# IRIS1304_v2_23.net
KiCad netlist of a schematic drawn in EAGLE
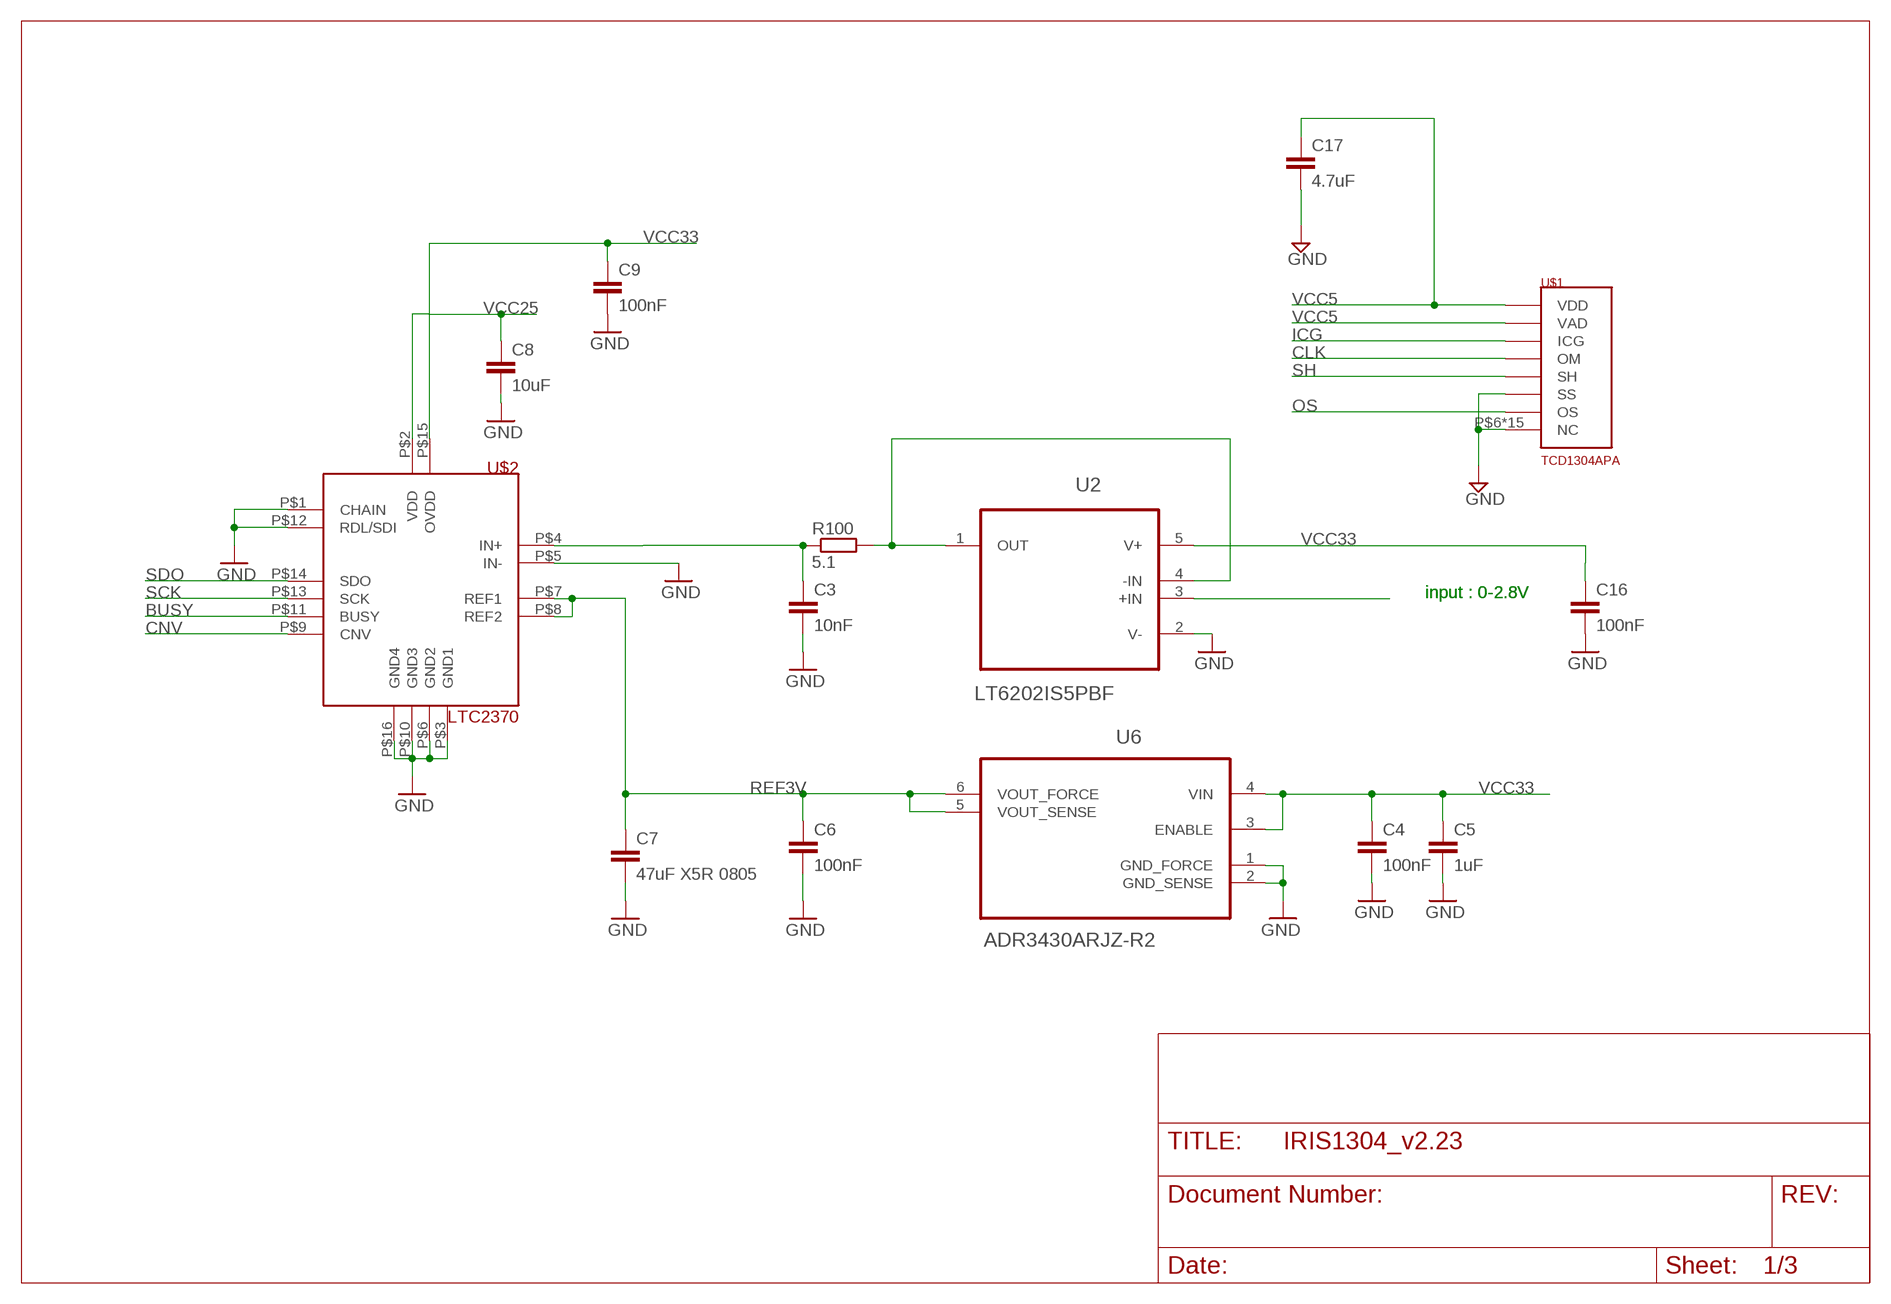
[diagram p0: schematic, sheet 1]
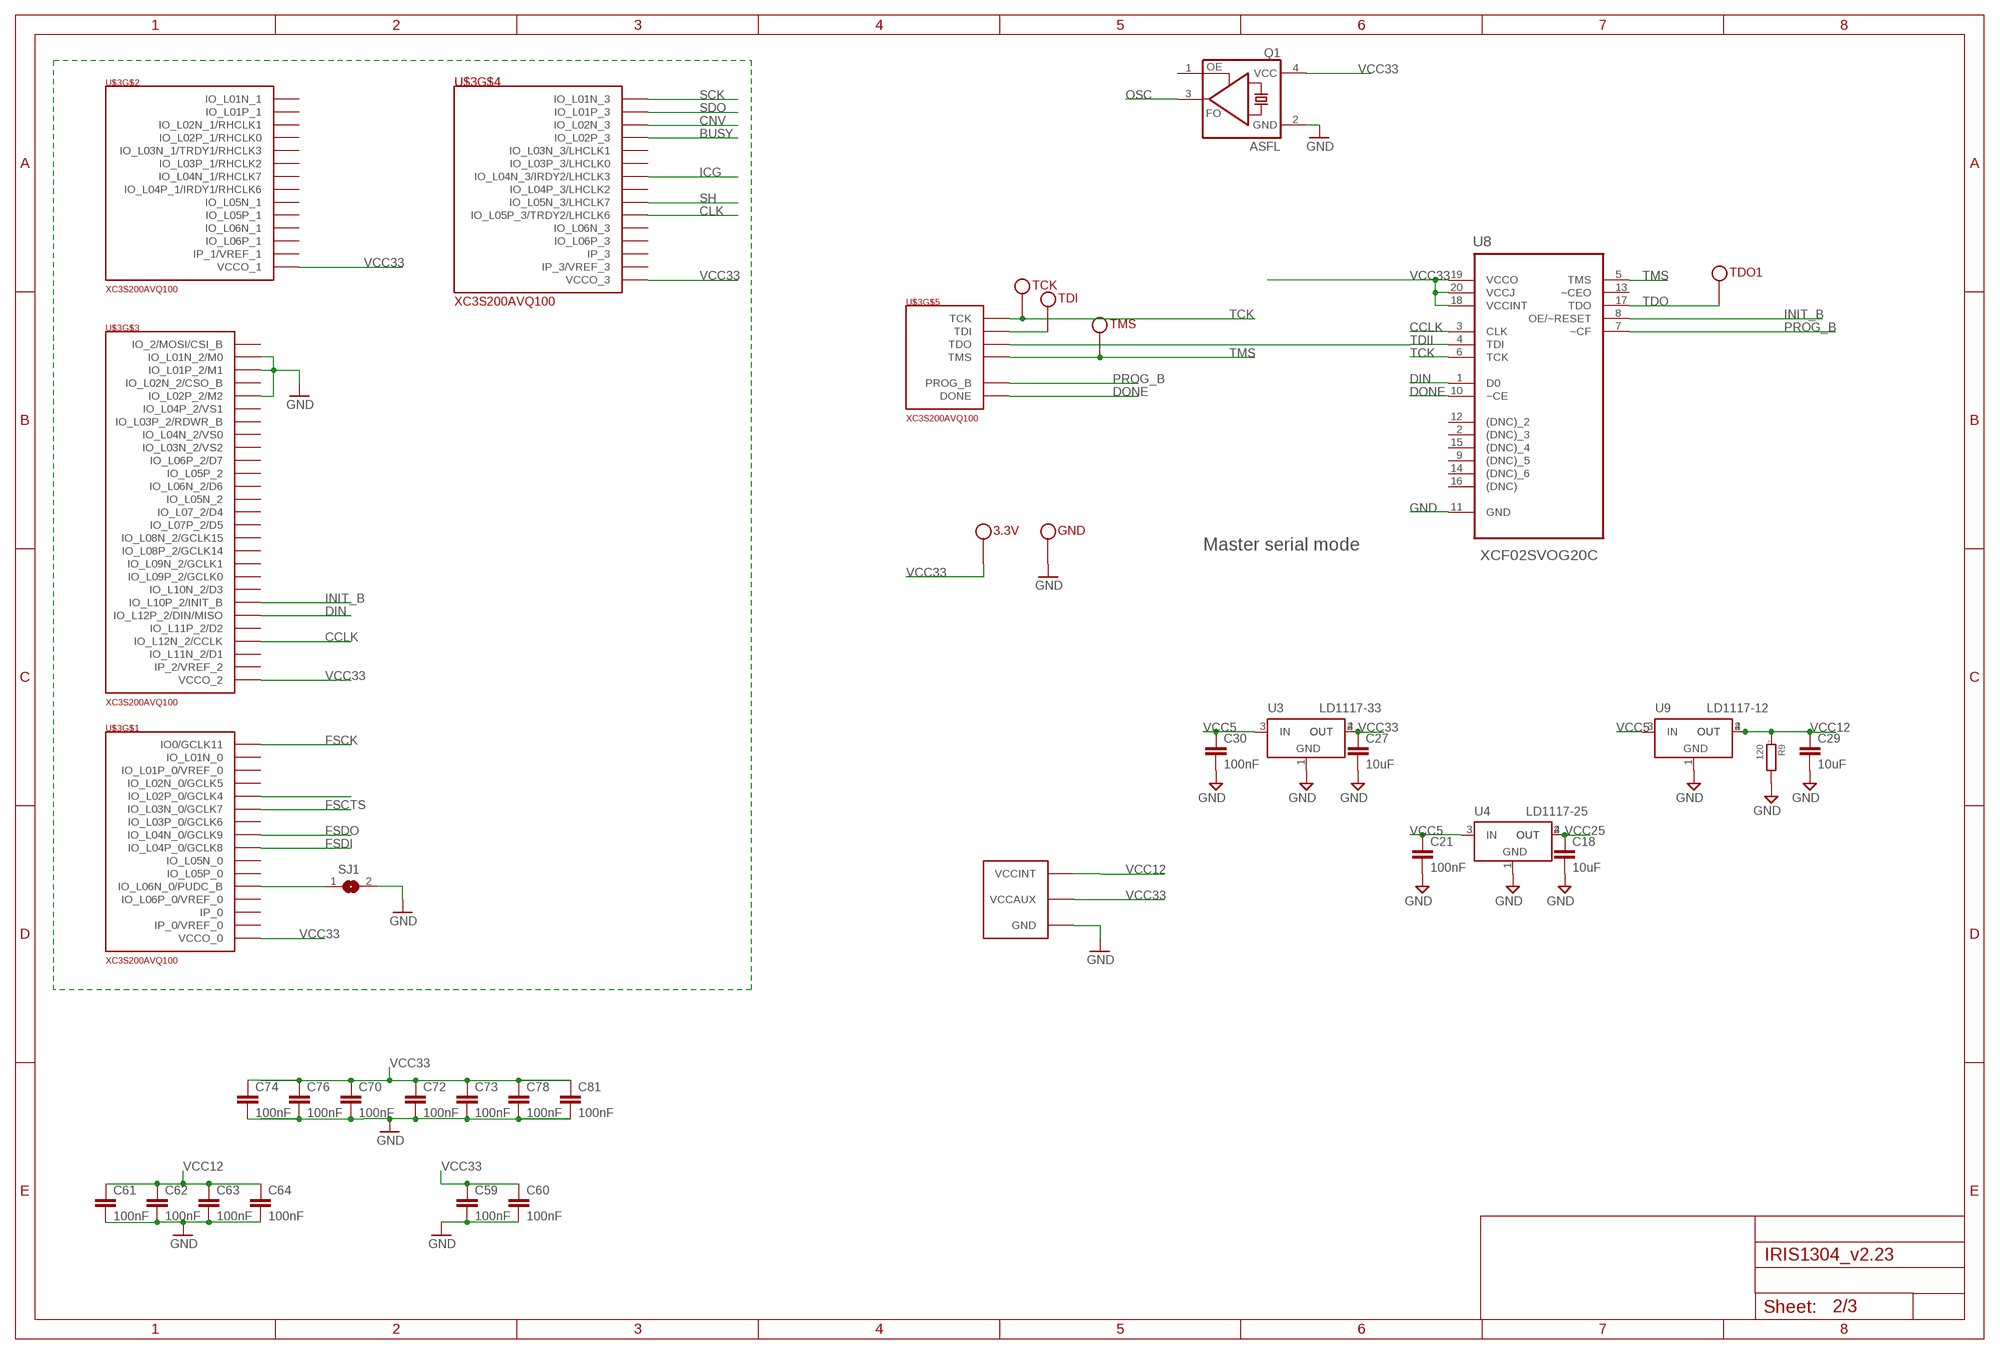
[diagram p1: schematic, sheet 2]
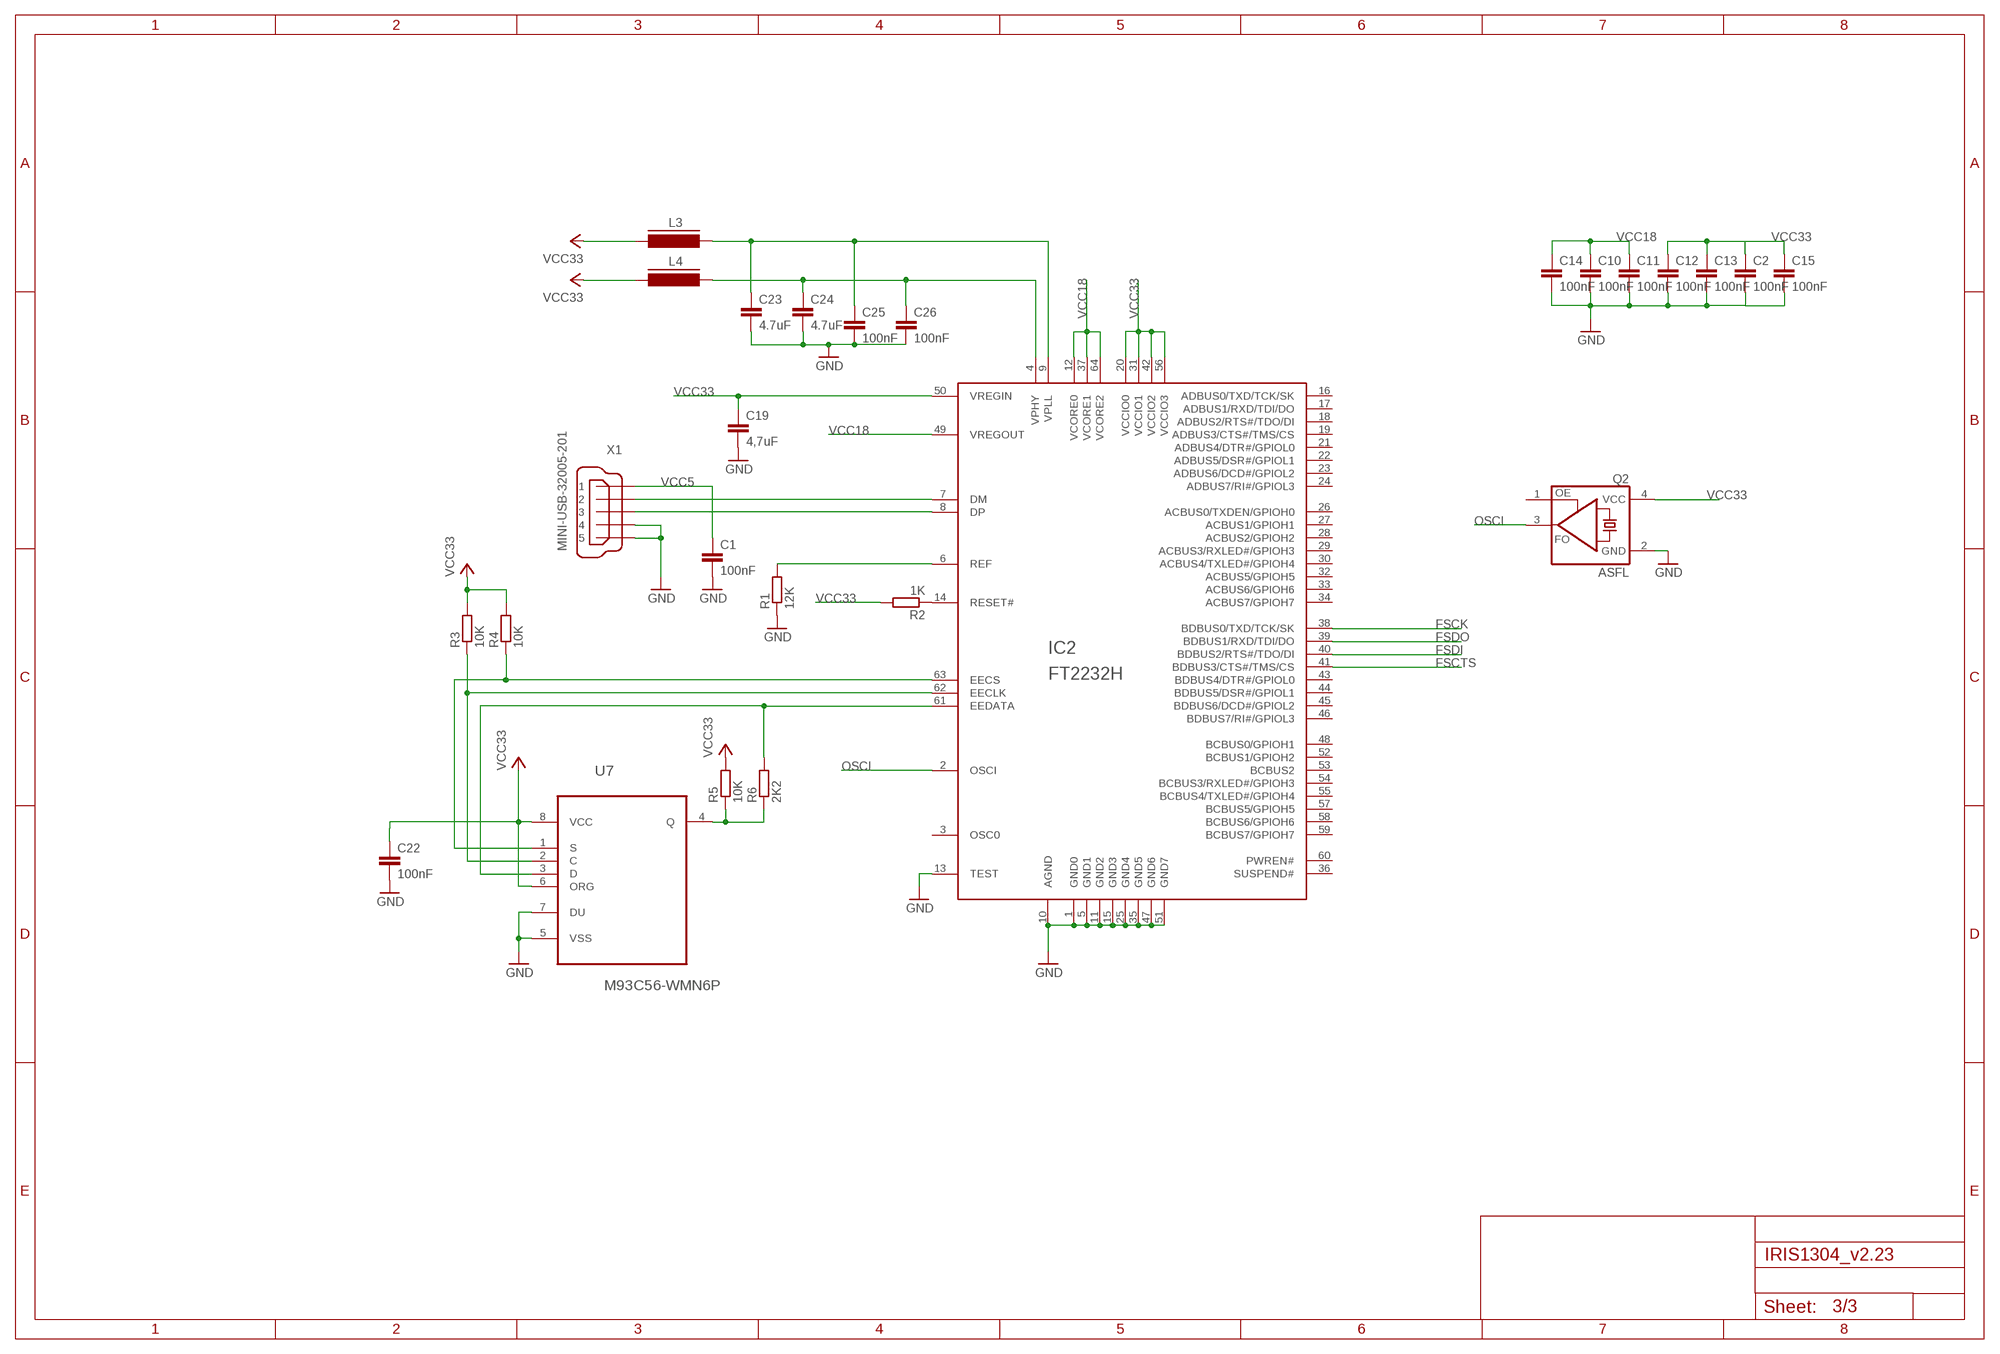
[diagram p2: schematic, sheet 3]

(export (version "E")
  (design (tool "Eeschema 10.0.6"))
  (components
    (comp (ref "C1")
      (value "100nF")
      (footprint "eagle-import:C0603")
      (fields (field (name "MF") "AVX") (field (name "MPN") "06033G104ZAT2A"))
      (libsource (lib "eagle-import") (part "C-EUC0603"))
    )
    (comp (ref "C2")
      (value "100nF")
      (footprint "eagle-import:C0603")
      (fields (field (name "MF") "AVX") (field (name "MPN") "06033G104ZAT2A"))
      (libsource (lib "eagle-import") (part "C-EUC0603"))
    )
    (comp (ref "C10")
      (value "100nF")
      (footprint "eagle-import:C0603")
      (fields (field (name "MF") "AVX") (field (name "MPN") "06033G104ZAT2A"))
      (libsource (lib "eagle-import") (part "C-EUC0603"))
    )
    (comp (ref "C11")
      (value "100nF")
      (footprint "eagle-import:C0603")
      (fields (field (name "MF") "AVX") (field (name "MPN") "06033G104ZAT2A"))
      (libsource (lib "eagle-import") (part "C-EUC0603"))
    )
    (comp (ref "C12")
      (value "100nF")
      (footprint "eagle-import:C0603")
      (fields (field (name "MF") "AVX") (field (name "MPN") "06033G104ZAT2A"))
      (libsource (lib "eagle-import") (part "C-EUC0603"))
    )
    (comp (ref "C13")
      (value "100nF")
      (footprint "eagle-import:C0603")
      (fields (field (name "MF") "AVX") (field (name "MPN") "06033G104ZAT2A"))
      (libsource (lib "eagle-import") (part "C-EUC0603"))
    )
    (comp (ref "C14")
      (value "100nF")
      (footprint "eagle-import:C0603")
      (fields (field (name "MF") "AVX") (field (name "MPN") "06033G104ZAT2A"))
      (libsource (lib "eagle-import") (part "C-EUC0603"))
    )
    (comp (ref "C15")
      (value "100nF")
      (footprint "eagle-import:C0603")
      (fields (field (name "MF") "AVX") (field (name "MPN") "06033G104ZAT2A"))
      (libsource (lib "eagle-import") (part "C-EUC0603"))
    )
    (comp (ref "C19")
      (value "4,7uF")
      (footprint "eagle-import:C0805")
      (fields (field (name "MF") "AVX") (field (name "MPN") "0805ZD335KAT2A"))
      (libsource (lib "eagle-import") (part "C-EUC0805"))
    )
    (comp (ref "C22")
      (value "100nF")
      (footprint "eagle-import:C0603")
      (fields (field (name "MF") "AVX") (field (name "MPN") "06033G104ZAT2A"))
      (libsource (lib "eagle-import") (part "C-EUC0603"))
    )
    (comp (ref "C23")
      (value "4.7uF")
      (footprint "eagle-import:C0603")
      (fields (field (name "MF") "YAGEO (PHYCOMP)") (field (name "MPN") "CC0603KRX5R6BB475"))
      (libsource (lib "eagle-import") (part "C-EUC0603"))
    )
    (comp (ref "C24")
      (value "4.7uF")
      (footprint "eagle-import:C0603")
      (fields (field (name "MF") "YAGEO (PHYCOMP)") (field (name "MPN") "CC0603KRX5R6BB475"))
      (libsource (lib "eagle-import") (part "C-EUC0603"))
    )
    (comp (ref "C25")
      (value "100nF")
      (footprint "eagle-import:C0603")
      (fields (field (name "MF") "AVX") (field (name "MPN") "06033G104ZAT2A"))
      (libsource (lib "eagle-import") (part "C-EUC0603"))
    )
    (comp (ref "C26")
      (value "100nF")
      (footprint "eagle-import:C0603")
      (fields (field (name "MF") "AVX") (field (name "MPN") "06033G104ZAT2A"))
      (libsource (lib "eagle-import") (part "C-EUC0603"))
    )
    (comp (ref "IC2")
      (value "FT2232H")
      (footprint "eagle-import:LQFP64")
      (fields (field (name "MF") "FTDI") (field (name "MPN") "FT2232HL-R"))
      (libsource (lib "eagle-import") (part "FT2232H"))
    )
    (comp (ref "L3")
      (value "FERRITE_BEAD805")
      (footprint "eagle-import:FB805")
      (libsource (lib "eagle-import") (part "FERRITE_BEAD805"))
    )
    (comp (ref "L4")
      (value "FERRITE_BEAD805")
      (footprint "eagle-import:FB805")
      (libsource (lib "eagle-import") (part "FERRITE_BEAD805"))
    )
    (comp (ref "Q2")
      (value "ASFL")
      (footprint "eagle-import:ASF")
      (fields
        (field (name "MPN") "ASFLM1-50.000MHZ-C-T")
        (field (name "MF") "ABRACON")
        (field (name "MPN_1") "ASFL1-12.000MHZ-EK-T")
        (field (name "OC_FARNELL") "7943088")
      )
      (libsource (lib "eagle-import") (part "ASFL"))
    )
    (comp (ref "R1")
      (value "12K")
      (footprint "eagle-import:R0603")
      (fields (field (name "MF") "TE CONNECTIVITY") (field (name "MPN") "CPF0201D12K1C1"))
      (libsource (lib "eagle-import") (part "R-EU_R0603"))
    )
    (comp (ref "R2")
      (value "1K")
      (footprint "eagle-import:R0603")
      (fields (field (name "MF") "VISHAY DRALORIC") (field (name "MPN") "CRCW06031K00FKEA"))
      (libsource (lib "eagle-import") (part "R-EU_R0603"))
    )
    (comp (ref "R3")
      (value "10K")
      (footprint "eagle-import:R0603")
      (fields (field (name "MF") "TE CONNECTIVITY / NEOHM") (field (name "MPN") "CPF0603F10KC1"))
      (libsource (lib "eagle-import") (part "R-EU_R0603"))
    )
    (comp (ref "R4")
      (value "10K")
      (footprint "eagle-import:R0603")
      (fields (field (name "MF") "TE CONNECTIVITY / NEOHM") (field (name "MPN") "CPF0603F10KC1"))
      (libsource (lib "eagle-import") (part "R-EU_R0603"))
    )
    (comp (ref "R5")
      (value "10K")
      (footprint "eagle-import:R0603")
      (fields (field (name "MF") "TE CONNECTIVITY / NEOHM") (field (name "MPN") "CPF0603F10KC1"))
      (libsource (lib "eagle-import") (part "R-EU_R0603"))
    )
    (comp (ref "R6")
      (value "2K2")
      (footprint "eagle-import:R0603")
      (fields (field (name "MF") "PANASONIC ELECTRONIC COMPONENTS") (field (name "MPN") "ERJP03F2201V"))
      (libsource (lib "eagle-import") (part "R-EU_R0603"))
    )
    (comp (ref "U7")
      (value "M93C56-WMN6P")
      (footprint "eagle-import:SOIC127P600X175-8N")
      (fields (field (name "MF") "STMICROELECTRONICS"))
      (libsource (lib "eagle-import") (part "M93C56-WMN6P"))
    )
    (comp (ref "X1")
      (value "MINI-USB-32005-201")
      (footprint "eagle-import:32005-201")
      (fields
        (field (name "MF") "WURTH ELEKTRONIK")
        (field (name "MPN") "65100516121")
        (field (name "OC_FARNELL") "1642036")
      )
      (libsource (lib "eagle-import") (part "MINI-USB-32005-201"))
    )
    (comp (ref "C3")
      (value "10nF")
      (footprint "eagle-import:C0603")
      (fields (field (name "MF") "AVX") (field (name "MPN") "06035G103ZAT2A"))
      (libsource (lib "eagle-import") (part "C-EUC0603"))
    )
    (comp (ref "C4")
      (value "100nF")
      (footprint "eagle-import:C0603")
      (fields (field (name "MF") "AVX") (field (name "MPN") "06033G104ZAT2A"))
      (libsource (lib "eagle-import") (part "C-EUC0603"))
    )
    (comp (ref "C5")
      (value "1uF")
      (footprint "eagle-import:C0603")
      (fields (field (name "MF") "KEMET") (field (name "MPN") "C0603C105K3PACTU"))
      (libsource (lib "eagle-import") (part "C-EUC0603"))
    )
    (comp (ref "C6")
      (value "100nF")
      (footprint "eagle-import:C0603")
      (fields (field (name "MF") "AVX") (field (name "MPN") "06033G104ZAT2A"))
      (libsource (lib "eagle-import") (part "C-EUC0603"))
    )
    (comp (ref "C7")
      (value "47uF X5R 0805")
      (footprint "eagle-import:C0805")
      (fields (field (name "MF") "KEMET") (field (name "MPN") "C0805C476M9PACTU"))
      (libsource (lib "eagle-import") (part "C-EUC0805"))
    )
    (comp (ref "C8")
      (value "10uF")
      (footprint "eagle-import:C0603")
      (fields (field (name "MF") "KEMET") (field (name "MPN") "C0603C106M9PACTU"))
      (libsource (lib "eagle-import") (part "C-EUC0603"))
    )
    (comp (ref "C9")
      (value "100nF")
      (footprint "eagle-import:C0603")
      (fields (field (name "MF") "AVX") (field (name "MPN") "06033G104ZAT2A"))
      (libsource (lib "eagle-import") (part "C-EUC0603"))
    )
    (comp (ref "C16")
      (value "100nF")
      (footprint "eagle-import:C0603")
      (fields (field (name "MF") "AVX") (field (name "MPN") "06033G104ZAT2A"))
      (libsource (lib "eagle-import") (part "C-EUC0603"))
    )
    (comp (ref "C17")
      (value "4.7uF")
      (footprint "eagle-import:C0603")
      (fields (field (name "MF") "YAGEO (PHYCOMP)") (field (name "MPN") "CC0603KRX5R6BB475"))
      (libsource (lib "eagle-import") (part "C-EUC0603"))
    )
    (comp (ref "R100")
      (value "5.1")
      (footprint "eagle-import:R0603")
      (fields (field (name "MF") "VISHAY DALE") (field (name "MPN") "CRCW06035R10FNEA"))
      (libsource (lib "eagle-import") (part "R-EU_R0603"))
    )
    (comp (ref "U$1")
      (value "TCD1304APA")
      (footprint "eagle-import:ILX511")
      (libsource (lib "eagle-import") (part "TCD1304APA"))
    )
    (comp (ref "U$2")
      (value "LTC2370")
      (footprint "eagle-import:MSOP-16")
      (fields (field (name "MF") "LINEAR TECHNOLOGY") (field (name "MPN") "LTC2370CMS-16"))
      (libsource (lib "eagle-import") (part "LTC2370"))
    )
    (comp (ref "U2")
      (value "LT6202IS5PBF")
      (footprint "eagle-import:SOT95P280X100-5N")
      (fields (field (name "MPN") "LT6202IS5#PBF") (field (name "MF") "LINEAR TECHNOLOGY"))
      (libsource (lib "eagle-import") (part "LT6202IS5PBF"))
    )
    (comp (ref "U6")
      (value "ADR3430ARJZ-R2")
      (footprint "eagle-import:SOT95P280X145-6N")
      (fields (field (name "MF") "ANALOG DEVICES"))
      (libsource (lib "eagle-import") (part "ADR3430ARJZ-R2"))
    )
    (comp (ref "3.3V")
      (value "TEST")
      (footprint "eagle-import:TEST")
      (fields (field (name "MF") "ITT CANNON") (field (name "MPN") "001-1007-040FB9"))
      (libsource (lib "eagle-import") (part "TEST"))
    )
    (comp (ref "C18")
      (value "10uF")
      (footprint "eagle-import:C0603")
      (fields (field (name "MF") "KEMET") (field (name "MPN") "C0603C106M9PACTU"))
      (libsource (lib "eagle-import") (part "C-EUC0603"))
    )
    (comp (ref "C21")
      (value "100nF")
      (footprint "eagle-import:C0603")
      (fields (field (name "MF") "AVX") (field (name "MPN") "06033G104ZAT2A"))
      (libsource (lib "eagle-import") (part "C-EUC0603"))
    )
    (comp (ref "C27")
      (value "10uF")
      (footprint "eagle-import:C0603")
      (fields (field (name "MF") "KEMET") (field (name "MPN") "C0603C106M9PACTU"))
      (libsource (lib "eagle-import") (part "C-EUC0603"))
    )
    (comp (ref "C29")
      (value "10uF")
      (footprint "eagle-import:C0603")
      (fields (field (name "MF") "KEMET") (field (name "MPN") "C0603C106M9PACTU"))
      (libsource (lib "eagle-import") (part "C-EUC0603"))
    )
    (comp (ref "C30")
      (value "100nF")
      (footprint "eagle-import:C0603")
      (fields (field (name "MF") "AVX") (field (name "MPN") "06033G104ZAT2A"))
      (libsource (lib "eagle-import") (part "C-EUC0603"))
    )
    (comp (ref "C59")
      (value "100nF")
      (footprint "eagle-import:C0603")
      (fields (field (name "MF") "AVX") (field (name "MPN") "06033G104ZAT2A"))
      (libsource (lib "eagle-import") (part "C-EUC0603"))
    )
    (comp (ref "C60")
      (value "100nF")
      (footprint "eagle-import:C0603")
      (fields (field (name "MF") "AVX") (field (name "MPN") "06033G104ZAT2A"))
      (libsource (lib "eagle-import") (part "C-EUC0603"))
    )
    (comp (ref "C61")
      (value "100nF")
      (footprint "eagle-import:C0603")
      (fields (field (name "MF") "AVX") (field (name "MPN") "06033G104ZAT2A"))
      (libsource (lib "eagle-import") (part "C-EUC0603"))
    )
    (comp (ref "C62")
      (value "100nF")
      (footprint "eagle-import:C0603")
      (fields (field (name "MF") "AVX") (field (name "MPN") "06033G104ZAT2A"))
      (libsource (lib "eagle-import") (part "C-EUC0603"))
    )
    (comp (ref "C63")
      (value "100nF")
      (footprint "eagle-import:C0603")
      (fields (field (name "MF") "AVX") (field (name "MPN") "06033G104ZAT2A"))
      (libsource (lib "eagle-import") (part "C-EUC0603"))
    )
    (comp (ref "C64")
      (value "100nF")
      (footprint "eagle-import:C0603")
      (fields (field (name "MF") "AVX") (field (name "MPN") "06033G104ZAT2A"))
      (libsource (lib "eagle-import") (part "C-EUC0603"))
    )
    (comp (ref "C70")
      (value "100nF")
      (footprint "eagle-import:C0603")
      (fields (field (name "MF") "AVX") (field (name "MPN") "06033G104ZAT2A"))
      (libsource (lib "eagle-import") (part "C-EUC0603"))
    )
    (comp (ref "C72")
      (value "100nF")
      (footprint "eagle-import:C0603")
      (fields (field (name "MF") "AVX") (field (name "MPN") "06033G104ZAT2A"))
      (libsource (lib "eagle-import") (part "C-EUC0603"))
    )
    (comp (ref "C73")
      (value "100nF")
      (footprint "eagle-import:C0603")
      (fields (field (name "MF") "AVX") (field (name "MPN") "06033G104ZAT2A"))
      (libsource (lib "eagle-import") (part "C-EUC0603"))
    )
    (comp (ref "C74")
      (value "100nF")
      (footprint "eagle-import:C0603")
      (fields (field (name "MF") "AVX") (field (name "MPN") "06033G104ZAT2A"))
      (libsource (lib "eagle-import") (part "C-EUC0603"))
    )
    (comp (ref "C76")
      (value "100nF")
      (footprint "eagle-import:C0603")
      (fields (field (name "MF") "AVX") (field (name "MPN") "06033G104ZAT2A"))
      (libsource (lib "eagle-import") (part "C-EUC0603"))
    )
    (comp (ref "C78")
      (value "100nF")
      (footprint "eagle-import:C0603")
      (fields (field (name "MF") "AVX") (field (name "MPN") "06033G104ZAT2A"))
      (libsource (lib "eagle-import") (part "C-EUC0603"))
    )
    (comp (ref "C81")
      (value "100nF")
      (footprint "eagle-import:C0603")
      (fields (field (name "MF") "AVX") (field (name "MPN") "06033G104ZAT2A"))
      (libsource (lib "eagle-import") (part "C-EUC0603"))
    )
    (comp (ref "GND")
      (value "TEST")
      (footprint "eagle-import:TEST")
      (fields (field (name "MF") "ITT CANNON") (field (name "MPN") "001-1007-040FB9"))
      (libsource (lib "eagle-import") (part "TEST"))
    )
    (comp (ref "Q1")
      (value "ASFL")
      (footprint "eagle-import:ASF")
      (fields
        (field (name "MPN") "ASFLM1-50.000MHZ-C-T")
        (field (name "MF") "ABRACON")
        (field (name "MPN_1") "ASFL1-12.000MHZ-EK-T")
        (field (name "OC_FARNELL") "7943088")
      )
      (libsource (lib "eagle-import") (part "ASFL"))
    )
    (comp (ref "R9")
      (value "120")
      (footprint "eagle-import:0805@1")
      (fields (field (name "MF") "TE CONNECTIVITY / SIGMA INDUCTORS") (field (name "MPN") "BMB2A0120AN1"))
      (libsource (lib "eagle-import") (part "R0805"))
    )
    (comp (ref "SJ1") (value "SJ") (footprint "eagle-import:SJ") (libsource (lib "eagle-import") (part "SJ")))
    (comp (ref "TCK")
      (value "TEST")
      (footprint "eagle-import:TEST")
      (fields (field (name "MF") "ITT CANNON") (field (name "MPN") "001-1007-040FB9"))
      (libsource (lib "eagle-import") (part "TEST"))
    )
    (comp (ref "TDI")
      (value "TEST")
      (footprint "eagle-import:TEST")
      (fields (field (name "MF") "ITT CANNON") (field (name "MPN") "001-1007-040FB9"))
      (libsource (lib "eagle-import") (part "TEST"))
    )
    (comp (ref "TDO1")
      (value "TEST")
      (footprint "eagle-import:TEST")
      (fields (field (name "MF") "ITT CANNON") (field (name "MPN") "001-1007-040FB9"))
      (libsource (lib "eagle-import") (part "TEST"))
    )
    (comp (ref "TMS")
      (value "TEST")
      (footprint "eagle-import:TEST")
      (fields (field (name "MF") "ITT CANNON") (field (name "MPN") "001-1007-040FB9"))
      (libsource (lib "eagle-import") (part "TEST"))
    )
    (comp (ref "U$3")
      (value "XC3S200AVQ100")
      (footprint "eagle-import:VQ100")
      (fields
        (field (name "MF") "XILINX")
        (field (name "MPN") "XC3S200A-4VQG100C")
        (field (name "OC_FARNELL") "1876204")
      )
      (libsource (lib "eagle-import") (part "XC3S200AVQ100"))
    )
    (comp (ref "U3")
      (value "LD1117-33")
      (footprint "eagle-import:SOT223")
      (fields (field (name "MF") "LINEAR TECHNOLOGY") (field (name "MPN") "LT1117CST-3.3#PBF"))
      (libsource (lib "eagle-import") (part "LD1117"))
    )
    (comp (ref "U4")
      (value "LD1117-25")
      (footprint "eagle-import:SOT223")
      (fields (field (name "MF") "STMICROELECTRONICS") (field (name "MPN") "LD1117S25TR"))
      (libsource (lib "eagle-import") (part "LD1117"))
    )
    (comp (ref "U8")
      (value "XCF02SVOG20C")
      (footprint "eagle-import:SOP65P640X119-20N")
      (fields (field (name "MF") "XILINX"))
      (libsource (lib "eagle-import") (part "XCF02SVOG20C"))
    )
    (comp (ref "U9")
      (value "LD1117-12")
      (footprint "eagle-import:SOT223")
      (fields (field (name "MF") "LINEAR TECHNOLOGY") (field (name "MPN") "LT1117IST#PBF"))
      (libsource (lib "eagle-import") (part "LD1117"))
    )
  )
  (nets
    (net (code "1") (name "BUSY") (class "Default")
      (node (ref "U$2") (pin "P$11") (pinfunction "BUSY_P$11") (pintype "bidirectional"))
      (node (ref "U$3") (pin "P5") (pinfunction "IO_L02P_3_P5") (pintype "bidirectional"))
    )
    (net (code "2") (name "CCLK") (class "Default")
      (node (ref "U$3") (pin "P53") (pinfunction "IO_L12N_2/CCLK_P53") (pintype "bidirectional"))
      (node (ref "U8") (pin "3") (pinfunction "CLK_3") (pintype "input"))
    )
    (net (code "3") (name "CLK") (class "Default")
      (node (ref "U$1") (pin "P$4") (pinfunction "OM_P$4") (pintype "bidirectional"))
      (node (ref "U$3") (pin "P15") (pinfunction "IO_L05P_3/TRDY2/LHCLK6_P15") (pintype "bidirectional"))
    )
    (net (code "4") (name "CNV") (class "Default")
      (node (ref "U$2") (pin "P$9") (pinfunction "CNV_P$9") (pintype "bidirectional"))
      (node (ref "U$3") (pin "P6") (pinfunction "IO_L02N_3_P6") (pintype "bidirectional"))
    )
    (net (code "5") (name "DIN") (class "Default")
      (node (ref "U$3") (pin "P51") (pinfunction "IO_L12P_2/DIN/MISO_P51") (pintype "bidirectional"))
      (node (ref "U8") (pin "1") (pinfunction "D0_1") (pintype "input"))
    )
    (net (code "6") (name "DONE") (class "Default")
      (node (ref "U$3") (pin "P54") (pinfunction "DONE_P54") (pintype "bidirectional"))
      (node (ref "U8") (pin "10") (pinfunction "~{CE}_10") (pintype "input"))
    )
    (net (code "7") (name "FSCK") (class "Default")
      (node (ref "IC2") (pin "38") (pinfunction "BDBUS0/TXD/TCK/SK_38") (pintype "bidirectional"))
      (node (ref "U$3") (pin "P90") (pinfunction "IO0/GCLK11_P90") (pintype "bidirectional"))
    )
    (net (code "8") (name "FSCTS") (class "Default")
      (node (ref "IC2") (pin "41") (pinfunction "BDBUS3/CTS#/TMS/CS_41") (pintype "bidirectional"))
      (node (ref "U$3") (pin "P86") (pinfunction "IO_L03N_0/GCLK7_P86") (pintype "bidirectional"))
    )
    (net (code "9") (name "FSDI") (class "Default")
      (node (ref "IC2") (pin "40") (pinfunction "BDBUS2/RTS#/TDO/DI_40") (pintype "bidirectional"))
      (node (ref "U$3") (pin "P88") (pinfunction "IO_L04P_0/GCLK8_P88") (pintype "bidirectional"))
    )
    (net (code "10") (name "FSDO") (class "Default")
      (node (ref "IC2") (pin "39") (pinfunction "BDBUS1/RXD/TDI/DO_39") (pintype "bidirectional"))
      (node (ref "U$3") (pin "P89") (pinfunction "IO_L04N_0/GCLK9_P89") (pintype "bidirectional"))
    )
    (net (code "11") (name "GND") (class "Default")
      (node (ref "C1") (pin "2") (pinfunction "2_2") (pintype "passive"))
      (node (ref "C10") (pin "2") (pinfunction "2_2") (pintype "passive"))
      (node (ref "C11") (pin "2") (pinfunction "2_2") (pintype "passive"))
      (node (ref "C12") (pin "2") (pinfunction "2_2") (pintype "passive"))
      (node (ref "C13") (pin "2") (pinfunction "2_2") (pintype "passive"))
      (node (ref "C14") (pin "2") (pinfunction "2_2") (pintype "passive"))
      (node (ref "C15") (pin "2") (pinfunction "2_2") (pintype "passive"))
      (node (ref "C16") (pin "2") (pinfunction "2_2") (pintype "passive"))
      (node (ref "C17") (pin "2") (pinfunction "2_2") (pintype "passive"))
      (node (ref "C18") (pin "2") (pinfunction "2_2") (pintype "passive"))
      (node (ref "C19") (pin "2") (pinfunction "2_2") (pintype "passive"))
      (node (ref "C2") (pin "2") (pinfunction "2_2") (pintype "passive"))
      (node (ref "C21") (pin "2") (pinfunction "2_2") (pintype "passive"))
      (node (ref "C22") (pin "2") (pinfunction "2_2") (pintype "passive"))
      (node (ref "C23") (pin "2") (pinfunction "2_2") (pintype "passive"))
      (node (ref "C24") (pin "2") (pinfunction "2_2") (pintype "passive"))
      (node (ref "C25") (pin "2") (pinfunction "2_2") (pintype "passive"))
      (node (ref "C26") (pin "2") (pinfunction "2_2") (pintype "passive"))
      (node (ref "C27") (pin "2") (pinfunction "2_2") (pintype "passive"))
      (node (ref "C29") (pin "2") (pinfunction "2_2") (pintype "passive"))
      (node (ref "C3") (pin "2") (pinfunction "2_2") (pintype "passive"))
      (node (ref "C30") (pin "2") (pinfunction "2_2") (pintype "passive"))
      (node (ref "C4") (pin "2") (pinfunction "2_2") (pintype "passive"))
      (node (ref "C5") (pin "2") (pinfunction "2_2") (pintype "passive"))
      (node (ref "C59") (pin "2") (pinfunction "2_2") (pintype "passive"))
      (node (ref "C6") (pin "2") (pinfunction "2_2") (pintype "passive"))
      (node (ref "C60") (pin "2") (pinfunction "2_2") (pintype "passive"))
      (node (ref "C61") (pin "2") (pinfunction "2_2") (pintype "passive"))
      (node (ref "C62") (pin "2") (pinfunction "2_2") (pintype "passive"))
      (node (ref "C63") (pin "2") (pinfunction "2_2") (pintype "passive"))
      (node (ref "C64") (pin "2") (pinfunction "2_2") (pintype "passive"))
      (node (ref "C7") (pin "2") (pinfunction "2_2") (pintype "passive"))
      (node (ref "C70") (pin "2") (pinfunction "2_2") (pintype "passive"))
      (node (ref "C72") (pin "2") (pinfunction "2_2") (pintype "passive"))
      (node (ref "C73") (pin "2") (pinfunction "2_2") (pintype "passive"))
      (node (ref "C74") (pin "2") (pinfunction "2_2") (pintype "passive"))
      (node (ref "C76") (pin "2") (pinfunction "2_2") (pintype "passive"))
      (node (ref "C78") (pin "2") (pinfunction "2_2") (pintype "passive"))
      (node (ref "C8") (pin "2") (pinfunction "2_2") (pintype "passive"))
      (node (ref "C81") (pin "2") (pinfunction "2_2") (pintype "passive"))
      (node (ref "C9") (pin "2") (pinfunction "2_2") (pintype "passive"))
      (node (ref "GND") (pin "P$1") (pinfunction "P$1_P$1") (pintype "bidirectional"))
      (node (ref "IC2") (pin "1") (pinfunction "GND0_1") (pintype "bidirectional"))
      (node (ref "IC2") (pin "10") (pinfunction "AGND_10") (pintype "bidirectional"))
      (node (ref "IC2") (pin "11") (pinfunction "GND2_11") (pintype "bidirectional"))
      (node (ref "IC2") (pin "13") (pinfunction "TEST_13") (pintype "bidirectional"))
      (node (ref "IC2") (pin "15") (pinfunction "GND3_15") (pintype "bidirectional"))
      (node (ref "IC2") (pin "25") (pinfunction "GND4_25") (pintype "bidirectional"))
      (node (ref "IC2") (pin "35") (pinfunction "GND5_35") (pintype "bidirectional"))
      (node (ref "IC2") (pin "47") (pinfunction "GND6_47") (pintype "bidirectional"))
      (node (ref "IC2") (pin "5") (pinfunction "GND1_5") (pintype "bidirectional"))
      (node (ref "IC2") (pin "51") (pinfunction "GND7_51") (pintype "bidirectional"))
      (node (ref "Q1") (pin "2") (pinfunction "GND_2") (pintype "power_in"))
      (node (ref "Q2") (pin "2") (pinfunction "GND_2") (pintype "power_in"))
      (node (ref "R1") (pin "1") (pinfunction "1_1") (pintype "passive"))
      (node (ref "R9") (pin "2") (pinfunction "2_2") (pintype "passive"))
      (node (ref "SJ1") (pin "2") (pinfunction "2_2") (pintype "passive"))
      (node (ref "U$1") (pin "P$10") (pinfunction "NC_P$10") (pintype "bidirectional"))
      (node (ref "U$1") (pin "P$11") (pinfunction "NC_P$11") (pintype "bidirectional"))
      (node (ref "U$1") (pin "P$12") (pinfunction "NC_P$12") (pintype "bidirectional"))
      (node (ref "U$1") (pin "P$13") (pinfunction "NC_P$13") (pintype "bidirectional"))
      (node (ref "U$1") (pin "P$14") (pinfunction "NC_P$14") (pintype "bidirectional"))
      (node (ref "U$1") (pin "P$15") (pinfunction "NC_P$15") (pintype "bidirectional"))
      (node (ref "U$1") (pin "P$16") (pinfunction "NC_P$16") (pintype "bidirectional"))
      (node (ref "U$1") (pin "P$17") (pinfunction "NC_P$17") (pintype "bidirectional"))
      (node (ref "U$1") (pin "P$18") (pinfunction "NC_P$18") (pintype "bidirectional"))
      (node (ref "U$1") (pin "P$19") (pinfunction "NC_P$19") (pintype "bidirectional"))
      (node (ref "U$1") (pin "P$20") (pinfunction "NC_P$20") (pintype "bidirectional"))
      (node (ref "U$1") (pin "P$22") (pinfunction "SS_P$22") (pintype "bidirectional"))
      (node (ref "U$1") (pin "P$6") (pinfunction "NC_P$6") (pintype "bidirectional"))
      (node (ref "U$1") (pin "P$7") (pinfunction "NC_P$7") (pintype "bidirectional"))
      (node (ref "U$1") (pin "P$8") (pinfunction "NC_P$8") (pintype "bidirectional"))
      (node (ref "U$1") (pin "P$9") (pinfunction "NC_P$9") (pintype "bidirectional"))
      (node (ref "U$2") (pin "P$1") (pinfunction "CHAIN_P$1") (pintype "bidirectional"))
      (node (ref "U$2") (pin "P$10") (pinfunction "GND3_P$10") (pintype "bidirectional"))
      (node (ref "U$2") (pin "P$12") (pinfunction "RDL/SDI_P$12") (pintype "bidirectional"))
      (node (ref "U$2") (pin "P$16") (pinfunction "GND4_P$16") (pintype "bidirectional"))
      (node (ref "U$2") (pin "P$3") (pinfunction "GND1_P$3") (pintype "bidirectional"))
      (node (ref "U$2") (pin "P$5") (pinfunction "IN-_P$5") (pintype "bidirectional"))
      (node (ref "U$2") (pin "P$6") (pinfunction "GND2_P$6") (pintype "bidirectional"))
      (node (ref "U$3") (pin "P14") (pinfunction "GND_P14") (pintype "bidirectional"))
      (node (ref "U$3") (pin "P18") (pinfunction "GND_P18") (pintype "bidirectional"))
      (node (ref "U$3") (pin "P23") (pinfunction "IO_L01P_2/M1_P23") (pintype "bidirectional"))
      (node (ref "U$3") (pin "P24") (pinfunction "IO_L02P_2/M2_P24") (pintype "bidirectional"))
      (node (ref "U$3") (pin "P25") (pinfunction "IO_L01N_2/M0_P25") (pintype "bidirectional"))
      (node (ref "U$3") (pin "P42") (pinfunction "GND_P42") (pintype "bidirectional"))
      (node (ref "U$3") (pin "P47") (pinfunction "GND_P47") (pintype "bidirectional"))
      (node (ref "U$3") (pin "P58") (pinfunction "GND_P58") (pintype "bidirectional"))
      (node (ref "U$3") (pin "P63") (pinfunction "GND_P63") (pintype "bidirectional"))
      (node (ref "U$3") (pin "P69") (pinfunction "GND_P69") (pintype "bidirectional"))
      (node (ref "U$3") (pin "P74") (pinfunction "GND_P74") (pintype "bidirectional"))
      (node (ref "U$3") (pin "P8") (pinfunction "GND_P8") (pintype "bidirectional"))
      (node (ref "U$3") (pin "P80") (pinfunction "GND_P80") (pintype "bidirectional"))
      (node (ref "U$3") (pin "P87") (pinfunction "GND_P87") (pintype "bidirectional"))
      (node (ref "U$3") (pin "P91") (pinfunction "GND_P91") (pintype "bidirectional"))
      (node (ref "U$3") (pin "P95") (pinfunction "GND_P95") (pintype "bidirectional"))
      (node (ref "U2") (pin "2") (pinfunction "V-_2") (pintype "power_in"))
      (node (ref "U3") (pin "1") (pinfunction "GND_1") (pintype "power_in"))
      (node (ref "U4") (pin "1") (pinfunction "GND_1") (pintype "power_in"))
      (node (ref "U6") (pin "1") (pinfunction "GND_FORCE_1") (pintype "passive"))
      (node (ref "U6") (pin "2") (pinfunction "GND_SENSE_2") (pintype "passive"))
      (node (ref "U7") (pin "5") (pinfunction "VSS_5") (pintype "power_in"))
      (node (ref "U7") (pin "7") (pinfunction "DU_7") (pintype "input"))
      (node (ref "U8") (pin "11") (pinfunction "GND_11") (pintype "passive"))
      (node (ref "U9") (pin "1") (pinfunction "GND_1") (pintype "power_in"))
      (node (ref "X1") (pin "4") (pinfunction "4_4") (pintype "passive"))
      (node (ref "X1") (pin "5") (pinfunction "5_5") (pintype "passive"))
    )
    (net (code "12") (name "ICG") (class "Default")
      (node (ref "U$1") (pin "P$3") (pinfunction "ICG_P$3") (pintype "bidirectional"))
      (node (ref "U$3") (pin "P13") (pinfunction "IO_L04N_3/IRDY2/LHCLK3_P13") (pintype "bidirectional"))
    )
    (net (code "13") (name "INIT_B") (class "Default")
      (node (ref "U$3") (pin "P48") (pinfunction "IO_L10P_2/INIT_B_P48") (pintype "bidirectional"))
      (node (ref "U8") (pin "8") (pinfunction "OE/~{RESET}_8") (pintype "bidirectional"))
    )
    (net (code "14") (name "Net-(IC2-DM)") (class "Default")
      (node (ref "IC2") (pin "7") (pinfunction "DM_7") (pintype "bidirectional"))
      (node (ref "X1") (pin "2") (pinfunction "2_2") (pintype "passive"))
    )
    (net (code "15") (name "Net-(IC2-DP)") (class "Default")
      (node (ref "IC2") (pin "8") (pinfunction "DP_8") (pintype "bidirectional"))
      (node (ref "X1") (pin "3") (pinfunction "3_3") (pintype "passive"))
    )
    (net (code "16") (name "Net-(IC2-EECLK)") (class "Default")
      (node (ref "IC2") (pin "62") (pinfunction "EECLK_62") (pintype "bidirectional"))
      (node (ref "R3") (pin "1") (pinfunction "1_1") (pintype "passive"))
      (node (ref "U7") (pin "2") (pinfunction "C_2") (pintype "input"))
    )
    (net (code "17") (name "Net-(IC2-EECS)") (class "Default")
      (node (ref "IC2") (pin "63") (pinfunction "EECS_63") (pintype "bidirectional"))
      (node (ref "R4") (pin "1") (pinfunction "1_1") (pintype "passive"))
      (node (ref "U7") (pin "1") (pinfunction "S_1") (pintype "input"))
    )
    (net (code "18") (name "Net-(IC2-EEDATA)") (class "Default")
      (node (ref "IC2") (pin "61") (pinfunction "EEDATA_61") (pintype "bidirectional"))
      (node (ref "R6") (pin "2") (pinfunction "2_2") (pintype "passive"))
      (node (ref "U7") (pin "3") (pinfunction "D_3") (pintype "input"))
    )
    (net (code "19") (name "Net-(IC2-REF)") (class "Default")
      (node (ref "IC2") (pin "6") (pinfunction "REF_6") (pintype "bidirectional"))
      (node (ref "R1") (pin "2") (pinfunction "2_2") (pintype "passive"))
    )
    (net (code "20") (name "Net-(IC2-RESET#)") (class "Default")
      (node (ref "IC2") (pin "14") (pinfunction "RESET#_14") (pintype "bidirectional"))
      (node (ref "R2") (pin "1") (pinfunction "1_1") (pintype "passive"))
    )
    (net (code "21") (name "Net-(IC2-VPHY)") (class "Default")
      (node (ref "C24") (pin "1") (pinfunction "1_1") (pintype "passive"))
      (node (ref "C26") (pin "1") (pinfunction "1_1") (pintype "passive"))
      (node (ref "IC2") (pin "4") (pinfunction "VPHY_4") (pintype "bidirectional"))
      (node (ref "L4") (pin "1") (pinfunction "1_1") (pintype "passive"))
    )
    (net (code "22") (name "Net-(IC2-VPLL)") (class "Default")
      (node (ref "C23") (pin "1") (pinfunction "1_1") (pintype "passive"))
      (node (ref "C25") (pin "1") (pinfunction "1_1") (pintype "passive"))
      (node (ref "IC2") (pin "9") (pinfunction "VPLL_9") (pintype "bidirectional"))
      (node (ref "L3") (pin "1") (pinfunction "1_1") (pintype "passive"))
    )
    (net (code "23") (name "Net-(U$2-IN+)") (class "Default")
      (node (ref "C3") (pin "1") (pinfunction "1_1") (pintype "passive"))
      (node (ref "R100") (pin "1") (pinfunction "1_1") (pintype "passive"))
      (node (ref "U$2") (pin "P$4") (pinfunction "IN+_P$4") (pintype "bidirectional"))
    )
    (net (code "24") (name "Net-(U$3A-IO_L06N_0{slash}PUDC_B)") (class "Default")
      (node (ref "SJ1") (pin "1") (pinfunction "1_1") (pintype "passive"))
      (node (ref "U$3") (pin "P99") (pinfunction "IO_L06N_0/PUDC_B_P99") (pintype "bidirectional"))
    )
    (net (code "25") (name "Net-(U$3E-TDI)") (class "Default")
      (node (ref "TDI") (pin "P$1") (pinfunction "P$1_P$1") (pintype "bidirectional"))
      (node (ref "U$3") (pin "P2") (pinfunction "TDI_P2") (pintype "bidirectional"))
    )
    (net (code "26") (name "Net-(U2--IN)") (class "Default")
      (node (ref "R100") (pin "2") (pinfunction "2_2") (pintype "passive"))
      (node (ref "U2") (pin "1") (pinfunction "OUT_1") (pintype "output"))
      (node (ref "U2") (pin "4") (pinfunction "-IN_4") (pintype "input"))
    )
    (net (code "27") (name "Net-(U7-Q)") (class "Default")
      (node (ref "R5") (pin "1") (pinfunction "1_1") (pintype "passive"))
      (node (ref "R6") (pin "1") (pinfunction "1_1") (pintype "passive"))
      (node (ref "U7") (pin "4") (pinfunction "Q_4") (pintype "output"))
    )
    (net (code "28") (name "OS") (class "Default")
      (node (ref "U$1") (pin "P$21") (pinfunction "OS_P$21") (pintype "bidirectional"))
      (node (ref "U2") (pin "3") (pinfunction "+IN_3") (pintype "input"))
    )
    (net (code "29") (name "OSC") (class "Default")
      (node (ref "Q1") (pin "3") (pinfunction "FO_3") (pintype "output"))
      (node (ref "U$3") (pin "P83") (pinfunction "IO_L02P_0/GCLK4_P83") (pintype "bidirectional"))
    )
    (net (code "30") (name "OSCI") (class "Default")
      (node (ref "IC2") (pin "2") (pinfunction "OSCI_2") (pintype "bidirectional"))
      (node (ref "Q2") (pin "3") (pinfunction "FO_3") (pintype "output"))
    )
    (net (code "31") (name "PROG_B") (class "Default")
      (node (ref "U$3") (pin "P100") (pinfunction "PROG_B_P100") (pintype "bidirectional"))
      (node (ref "U8") (pin "7") (pinfunction "~{CF}_7") (pintype "bidirectional"))
    )
    (net (code "32") (name "REF3V") (class "Default")
      (node (ref "C6") (pin "1") (pinfunction "1_1") (pintype "passive"))
      (node (ref "C7") (pin "1") (pinfunction "1_1") (pintype "passive"))
      (node (ref "U$2") (pin "P$7") (pinfunction "REF1_P$7") (pintype "bidirectional"))
      (node (ref "U$2") (pin "P$8") (pinfunction "REF2_P$8") (pintype "bidirectional"))
      (node (ref "U6") (pin "5") (pinfunction "VOUT_SENSE_5") (pintype "output"))
      (node (ref "U6") (pin "6") (pinfunction "VOUT_FORCE_6") (pintype "output"))
    )
    (net (code "33") (name "SCK") (class "Default")
      (node (ref "U$2") (pin "P$13") (pinfunction "SCK_P$13") (pintype "bidirectional"))
      (node (ref "U$3") (pin "P4") (pinfunction "IO_L01N_3_P4") (pintype "bidirectional"))
    )
    (net (code "34") (name "SDO") (class "Default")
      (node (ref "U$2") (pin "P$14") (pinfunction "SDO_P$14") (pintype "bidirectional"))
      (node (ref "U$3") (pin "P3") (pinfunction "IO_L01P_3_P3") (pintype "bidirectional"))
    )
    (net (code "35") (name "SH") (class "Default")
      (node (ref "U$1") (pin "P$5") (pinfunction "SH_P$5") (pintype "bidirectional"))
      (node (ref "U$3") (pin "P16") (pinfunction "IO_L05N_3/LHCLK7_P16") (pintype "bidirectional"))
    )
    (net (code "36") (name "TCK") (class "Default")
      (node (ref "TCK") (pin "P$1") (pinfunction "P$1_P$1") (pintype "bidirectional"))
      (node (ref "U$3") (pin "P76") (pinfunction "TCK_P76") (pintype "bidirectional"))
      (node (ref "U8") (pin "6") (pinfunction "TCK_6") (pintype "input"))
    )
    (net (code "37") (name "TDII") (class "Default")
      (node (ref "U$3") (pin "P75") (pinfunction "TDO_P75") (pintype "bidirectional"))
      (node (ref "U8") (pin "4") (pinfunction "TDI_4") (pintype "input"))
    )
    (net (code "38") (name "TDO") (class "Default")
      (node (ref "TDO1") (pin "P$1") (pinfunction "P$1_P$1") (pintype "bidirectional"))
      (node (ref "U8") (pin "17") (pinfunction "TDO_17") (pintype "output"))
    )
    (net (code "39") (name "TMS") (class "Default")
      (node (ref "TMS") (pin "P$1") (pinfunction "P$1_P$1") (pintype "bidirectional"))
      (node (ref "U$3") (pin "P1") (pinfunction "TMS_P1") (pintype "bidirectional"))
      (node (ref "U8") (pin "5") (pinfunction "TMS_5") (pintype "input"))
    )
    (net (code "40") (name "VCC5") (class "Default")
      (node (ref "C1") (pin "1") (pinfunction "1_1") (pintype "passive"))
      (node (ref "C17") (pin "1") (pinfunction "1_1") (pintype "passive"))
      (node (ref "C21") (pin "1") (pinfunction "1_1") (pintype "passive"))
      (node (ref "C30") (pin "1") (pinfunction "1_1") (pintype "passive"))
      (node (ref "U$1") (pin "P$1") (pinfunction "VDD_P$1") (pintype "bidirectional"))
      (node (ref "U$1") (pin "P$2") (pinfunction "VAD_P$2") (pintype "bidirectional"))
      (node (ref "U3") (pin "3") (pinfunction "IN_3") (pintype "input"))
      (node (ref "U4") (pin "3") (pinfunction "IN_3") (pintype "input"))
      (node (ref "U9") (pin "3") (pinfunction "IN_3") (pintype "input"))
      (node (ref "X1") (pin "1") (pinfunction "1_1") (pintype "passive"))
    )
    (net (code "41") (name "VCC12") (class "Default")
      (node (ref "C29") (pin "1") (pinfunction "1_1") (pintype "passive"))
      (node (ref "C61") (pin "1") (pinfunction "1_1") (pintype "passive"))
      (node (ref "C62") (pin "1") (pinfunction "1_1") (pintype "passive"))
      (node (ref "C63") (pin "1") (pinfunction "1_1") (pintype "passive"))
      (node (ref "C64") (pin "1") (pinfunction "1_1") (pintype "passive"))
      (node (ref "R9") (pin "1") (pinfunction "1_1") (pintype "passive"))
      (node (ref "U$3") (pin "P17") (pinfunction "VCCINT_P17") (pintype "bidirectional"))
      (node (ref "U$3") (pin "P38") (pinfunction "VCCINT_P38") (pintype "bidirectional"))
      (node (ref "U$3") (pin "P66") (pinfunction "VCCINT_P66") (pintype "bidirectional"))
      (node (ref "U$3") (pin "P81") (pinfunction "VCCINT_P81") (pintype "bidirectional"))
      (node (ref "U9") (pin "2") (pinfunction "OUT_2") (pintype "output"))
      (node (ref "U9") (pin "4") (pinfunction "OUT_4") (pintype "output"))
    )
    (net (code "42") (name "VCC18") (class "Default")
      (node (ref "C10") (pin "1") (pinfunction "1_1") (pintype "passive"))
      (node (ref "C11") (pin "1") (pinfunction "1_1") (pintype "passive"))
      (node (ref "C14") (pin "1") (pinfunction "1_1") (pintype "passive"))
      (node (ref "IC2") (pin "12") (pinfunction "VCORE0_12") (pintype "bidirectional"))
      (node (ref "IC2") (pin "37") (pinfunction "VCORE1_37") (pintype "bidirectional"))
      (node (ref "IC2") (pin "49") (pinfunction "VREGOUT_49") (pintype "bidirectional"))
      (node (ref "IC2") (pin "64") (pinfunction "VCORE2_64") (pintype "bidirectional"))
    )
    (net (code "43") (name "VCC25") (class "Default")
      (node (ref "C18") (pin "1") (pinfunction "1_1") (pintype "passive"))
      (node (ref "C8") (pin "1") (pinfunction "1_1") (pintype "passive"))
      (node (ref "U$2") (pin "P$2") (pinfunction "VDD_P$2") (pintype "bidirectional"))
      (node (ref "U4") (pin "2") (pinfunction "OUT_2") (pintype "output"))
      (node (ref "U4") (pin "4") (pinfunction "OUT_4") (pintype "output"))
    )
    (net (code "44") (name "VCC33") (class "Default")
      (node (ref "3.3V") (pin "P$1") (pinfunction "P$1_P$1") (pintype "bidirectional"))
      (node (ref "C12") (pin "1") (pinfunction "1_1") (pintype "passive"))
      (node (ref "C13") (pin "1") (pinfunction "1_1") (pintype "passive"))
      (node (ref "C15") (pin "1") (pinfunction "1_1") (pintype "passive"))
      (node (ref "C16") (pin "1") (pinfunction "1_1") (pintype "passive"))
      (node (ref "C19") (pin "1") (pinfunction "1_1") (pintype "passive"))
      (node (ref "C2") (pin "1") (pinfunction "1_1") (pintype "passive"))
      (node (ref "C22") (pin "1") (pinfunction "1_1") (pintype "passive"))
      (node (ref "C27") (pin "1") (pinfunction "1_1") (pintype "passive"))
      (node (ref "C4") (pin "1") (pinfunction "1_1") (pintype "passive"))
      (node (ref "C5") (pin "1") (pinfunction "1_1") (pintype "passive"))
      (node (ref "C59") (pin "1") (pinfunction "1_1") (pintype "passive"))
      (node (ref "C60") (pin "1") (pinfunction "1_1") (pintype "passive"))
      (node (ref "C70") (pin "1") (pinfunction "1_1") (pintype "passive"))
      (node (ref "C72") (pin "1") (pinfunction "1_1") (pintype "passive"))
      (node (ref "C73") (pin "1") (pinfunction "1_1") (pintype "passive"))
      (node (ref "C74") (pin "1") (pinfunction "1_1") (pintype "passive"))
      (node (ref "C76") (pin "1") (pinfunction "1_1") (pintype "passive"))
      (node (ref "C78") (pin "1") (pinfunction "1_1") (pintype "passive"))
      (node (ref "C81") (pin "1") (pinfunction "1_1") (pintype "passive"))
      (node (ref "C9") (pin "1") (pinfunction "1_1") (pintype "passive"))
      (node (ref "IC2") (pin "20") (pinfunction "VCCIO0_20") (pintype "bidirectional"))
      (node (ref "IC2") (pin "31") (pinfunction "VCCIO1_31") (pintype "bidirectional"))
      (node (ref "IC2") (pin "42") (pinfunction "VCCIO2_42") (pintype "bidirectional"))
      (node (ref "IC2") (pin "50") (pinfunction "VREGIN_50") (pintype "bidirectional"))
      (node (ref "IC2") (pin "56") (pinfunction "VCCIO3_56") (pintype "bidirectional"))
      (node (ref "L3") (pin "2") (pinfunction "2_2") (pintype "passive"))
      (node (ref "L4") (pin "2") (pinfunction "2_2") (pintype "passive"))
      (node (ref "Q1") (pin "4") (pinfunction "VCC_4") (pintype "power_in"))
      (node (ref "Q2") (pin "4") (pinfunction "VCC_4") (pintype "power_in"))
      (node (ref "R2") (pin "2") (pinfunction "2_2") (pintype "passive"))
      (node (ref "R3") (pin "2") (pinfunction "2_2") (pintype "passive"))
      (node (ref "R4") (pin "2") (pinfunction "2_2") (pintype "passive"))
      (node (ref "R5") (pin "2") (pinfunction "2_2") (pintype "passive"))
      (node (ref "U$2") (pin "P$15") (pinfunction "OVDD_P$15") (pintype "bidirectional"))
      (node (ref "U$3") (pin "P11") (pinfunction "VCCO_3_P11") (pintype "bidirectional"))
      (node (ref "U$3") (pin "P22") (pinfunction "VCCAUX_P22") (pintype "bidirectional"))
      (node (ref "U$3") (pin "P26") (pinfunction "VCCO_2_P26") (pintype "bidirectional"))
      (node (ref "U$3") (pin "P45") (pinfunction "VCCO_2_P45") (pintype "bidirectional"))
      (node (ref "U$3") (pin "P55") (pinfunction "VCCAUX_P55") (pintype "bidirectional"))
      (node (ref "U$3") (pin "P67") (pinfunction "VCCO_1_P67") (pintype "bidirectional"))
      (node (ref "U$3") (pin "P79") (pinfunction "VCCO_0_P79") (pintype "bidirectional"))
      (node (ref "U$3") (pin "P92") (pinfunction "VCCAUX_P92") (pintype "bidirectional"))
      (node (ref "U$3") (pin "P96") (pinfunction "VCCO_0_P96") (pintype "bidirectional"))
      (node (ref "U2") (pin "5") (pinfunction "V+_5") (pintype "power_in"))
      (node (ref "U3") (pin "2") (pinfunction "OUT_2") (pintype "output"))
      (node (ref "U3") (pin "4") (pinfunction "OUT_4") (pintype "output"))
      (node (ref "U6") (pin "3") (pinfunction "ENABLE_3") (pintype "input"))
      (node (ref "U6") (pin "4") (pinfunction "VIN_4") (pintype "input"))
      (node (ref "U7") (pin "6") (pinfunction "ORG_6") (pintype "input"))
      (node (ref "U7") (pin "8") (pinfunction "VCC_8") (pintype "power_in"))
      (node (ref "U8") (pin "18") (pinfunction "VCCINT_18") (pintype "power_in"))
      (node (ref "U8") (pin "19") (pinfunction "VCCO_19") (pintype "power_in"))
      (node (ref "U8") (pin "20") (pinfunction "VCCJ_20") (pintype "power_in"))
    )
    (net (code "45") (name "unconnected-(IC2-ACBUS0{slash}TXDEN{slash}GPIOH0-Pad26)") (class "Default")
      (node (ref "IC2") (pin "26") (pinfunction "ACBUS0/TXDEN/GPIOH0_26") (pintype "bidirectional"))
    )
    (net (code "46") (name "unconnected-(IC2-ACBUS1{slash}GPIOH1-Pad27)") (class "Default")
      (node (ref "IC2") (pin "27") (pinfunction "ACBUS1/GPIOH1_27") (pintype "bidirectional"))
    )
    (net (code "47") (name "unconnected-(IC2-ACBUS2{slash}GPIOH2-Pad28)") (class "Default")
      (node (ref "IC2") (pin "28") (pinfunction "ACBUS2/GPIOH2_28") (pintype "bidirectional"))
    )
    (net (code "48") (name "unconnected-(IC2-ACBUS3{slash}RXLED#{slash}GPIOH3-Pad29)") (class "Default")
      (node (ref "IC2") (pin "29") (pinfunction "ACBUS3/RXLED#/GPIOH3_29") (pintype "bidirectional"))
    )
    (net (code "49") (name "unconnected-(IC2-ACBUS4{slash}TXLED#{slash}GPIOH4-Pad30)") (class "Default")
      (node (ref "IC2") (pin "30") (pinfunction "ACBUS4/TXLED#/GPIOH4_30") (pintype "bidirectional"))
    )
    (net (code "50") (name "unconnected-(IC2-ACBUS5{slash}GPIOH5-Pad32)") (class "Default")
      (node (ref "IC2") (pin "32") (pinfunction "ACBUS5/GPIOH5_32") (pintype "bidirectional"))
    )
    (net (code "51") (name "unconnected-(IC2-ACBUS6{slash}GPIOH6-Pad33)") (class "Default")
      (node (ref "IC2") (pin "33") (pinfunction "ACBUS6/GPIOH6_33") (pintype "bidirectional"))
    )
    (net (code "52") (name "unconnected-(IC2-ACBUS7{slash}GPIOH7-Pad34)") (class "Default")
      (node (ref "IC2") (pin "34") (pinfunction "ACBUS7/GPIOH7_34") (pintype "bidirectional"))
    )
    (net (code "53") (name "unconnected-(IC2-ADBUS0{slash}TXD{slash}TCK{slash}SK-Pad16)") (class "Default")
      (node (ref "IC2") (pin "16") (pinfunction "ADBUS0/TXD/TCK/SK_16") (pintype "bidirectional"))
    )
    (net (code "54") (name "unconnected-(IC2-ADBUS1{slash}RXD{slash}TDI{slash}DO-Pad17)") (class "Default")
      (node (ref "IC2") (pin "17") (pinfunction "ADBUS1/RXD/TDI/DO_17") (pintype "bidirectional"))
    )
    (net (code "55") (name "unconnected-(IC2-ADBUS2{slash}RTS#{slash}TDO{slash}DI-Pad18)") (class "Default")
      (node (ref "IC2") (pin "18") (pinfunction "ADBUS2/RTS#/TDO/DI_18") (pintype "bidirectional"))
    )
    (net (code "56") (name "unconnected-(IC2-ADBUS3{slash}CTS#{slash}TMS{slash}CS-Pad19)") (class "Default")
      (node (ref "IC2") (pin "19") (pinfunction "ADBUS3/CTS#/TMS/CS_19") (pintype "bidirectional"))
    )
    (net (code "57") (name "unconnected-(IC2-ADBUS4{slash}DTR#{slash}GPIOL0-Pad21)") (class "Default")
      (node (ref "IC2") (pin "21") (pinfunction "ADBUS4/DTR#/GPIOL0_21") (pintype "bidirectional"))
    )
    (net (code "58") (name "unconnected-(IC2-ADBUS5{slash}DSR#{slash}GPIOL1-Pad22)") (class "Default")
      (node (ref "IC2") (pin "22") (pinfunction "ADBUS5/DSR#/GPIOL1_22") (pintype "bidirectional"))
    )
    (net (code "59") (name "unconnected-(IC2-ADBUS6{slash}DCD#{slash}GPIOL2-Pad23)") (class "Default")
      (node (ref "IC2") (pin "23") (pinfunction "ADBUS6/DCD#/GPIOL2_23") (pintype "bidirectional"))
    )
    (net (code "60") (name "unconnected-(IC2-ADBUS7{slash}RI#{slash}GPIOL3-Pad24)") (class "Default")
      (node (ref "IC2") (pin "24") (pinfunction "ADBUS7/RI#/GPIOL3_24") (pintype "bidirectional"))
    )
    (net (code "61") (name "unconnected-(IC2-BCBUS0{slash}GPIOH1-Pad48)") (class "Default")
      (node (ref "IC2") (pin "48") (pinfunction "BCBUS0/GPIOH1_48") (pintype "bidirectional"))
    )
    (net (code "62") (name "unconnected-(IC2-BCBUS1{slash}GPIOH2-Pad52)") (class "Default")
      (node (ref "IC2") (pin "52") (pinfunction "BCBUS1/GPIOH2_52") (pintype "bidirectional"))
    )
    (net (code "63") (name "unconnected-(IC2-BCBUS2-Pad53)") (class "Default")
      (node (ref "IC2") (pin "53") (pinfunction "BCBUS2_53") (pintype "bidirectional"))
    )
    (net (code "64") (name "unconnected-(IC2-BCBUS3{slash}RXLED#{slash}GPIOH3-Pad54)") (class "Default")
      (node (ref "IC2") (pin "54") (pinfunction "BCBUS3/RXLED#/GPIOH3_54") (pintype "bidirectional"))
    )
    (net (code "65") (name "unconnected-(IC2-BCBUS4{slash}TXLED#{slash}GPIOH4-Pad55)") (class "Default")
      (node (ref "IC2") (pin "55") (pinfunction "BCBUS4/TXLED#/GPIOH4_55") (pintype "bidirectional"))
    )
    (net (code "66") (name "unconnected-(IC2-BCBUS5{slash}GPIOH5-Pad57)") (class "Default")
      (node (ref "IC2") (pin "57") (pinfunction "BCBUS5/GPIOH5_57") (pintype "bidirectional"))
    )
    (net (code "67") (name "unconnected-(IC2-BCBUS6{slash}GPIOH6-Pad58)") (class "Default")
      (node (ref "IC2") (pin "58") (pinfunction "BCBUS6/GPIOH6_58") (pintype "bidirectional"))
    )
    (net (code "68") (name "unconnected-(IC2-BCBUS7{slash}GPIOH7-Pad59)") (class "Default")
      (node (ref "IC2") (pin "59") (pinfunction "BCBUS7/GPIOH7_59") (pintype "bidirectional"))
    )
    (net (code "69") (name "unconnected-(IC2-BDBUS4{slash}DTR#{slash}GPIOL0-Pad43)") (class "Default")
      (node (ref "IC2") (pin "43") (pinfunction "BDBUS4/DTR#/GPIOL0_43") (pintype "bidirectional"))
    )
    (net (code "70") (name "unconnected-(IC2-BDBUS5{slash}DSR#{slash}GPIOL1-Pad44)") (class "Default")
      (node (ref "IC2") (pin "44") (pinfunction "BDBUS5/DSR#/GPIOL1_44") (pintype "bidirectional"))
    )
    (net (code "71") (name "unconnected-(IC2-BDBUS6{slash}DCD#{slash}GPIOL2-Pad45)") (class "Default")
      (node (ref "IC2") (pin "45") (pinfunction "BDBUS6/DCD#/GPIOL2_45") (pintype "bidirectional"))
    )
    (net (code "72") (name "unconnected-(IC2-BDBUS7{slash}RI#{slash}GPIOL3-Pad46)") (class "Default")
      (node (ref "IC2") (pin "46") (pinfunction "BDBUS7/RI#/GPIOL3_46") (pintype "bidirectional"))
    )
    (net (code "73") (name "unconnected-(IC2-OSC0-Pad3)") (class "Default")
      (node (ref "IC2") (pin "3") (pinfunction "OSC0_3") (pintype "bidirectional"))
    )
    (net (code "74") (name "unconnected-(IC2-PWREN#-Pad60)") (class "Default")
      (node (ref "IC2") (pin "60") (pinfunction "PWREN#_60") (pintype "bidirectional"))
    )
    (net (code "75") (name "unconnected-(IC2-SUSPEND#-Pad36)") (class "Default")
      (node (ref "IC2") (pin "36") (pinfunction "SUSPEND#_36") (pintype "bidirectional"))
    )
    (net (code "76") (name "unconnected-(Q1-OE-Pad1)") (class "Default")
      (node (ref "Q1") (pin "1") (pinfunction "OE_1") (pintype "input"))
    )
    (net (code "77") (name "unconnected-(Q2-OE-Pad1)") (class "Default")
      (node (ref "Q2") (pin "1") (pinfunction "OE_1") (pintype "input"))
    )
    (net (code "78") (name "unconnected-(U$3A-IO_L01N_0-PadP78)") (class "Default")
      (node (ref "U$3") (pin "P78") (pinfunction "IO_L01N_0_P78") (pintype "bidirectional"))
    )
    (net (code "79") (name "unconnected-(U$3A-IO_L01P_0{slash}VREF_0-PadP77)") (class "Default")
      (node (ref "U$3") (pin "P77") (pinfunction "IO_L01P_0/VREF_0_P77") (pintype "bidirectional"))
    )
    (net (code "80") (name "unconnected-(U$3A-IO_L02N_0{slash}GCLK5-PadP84)") (class "Default")
      (node (ref "U$3") (pin "P84") (pinfunction "IO_L02N_0/GCLK5_P84") (pintype "bidirectional"))
    )
    (net (code "81") (name "unconnected-(U$3A-IO_L03P_0{slash}GCLK6-PadP85)") (class "Default")
      (node (ref "U$3") (pin "P85") (pinfunction "IO_L03P_0/GCLK6_P85") (pintype "bidirectional"))
    )
    (net (code "82") (name "unconnected-(U$3A-IO_L05N_0-PadP94)") (class "Default")
      (node (ref "U$3") (pin "P94") (pinfunction "IO_L05N_0_P94") (pintype "bidirectional"))
    )
    (net (code "83") (name "unconnected-(U$3A-IO_L05P_0-PadP93)") (class "Default")
      (node (ref "U$3") (pin "P93") (pinfunction "IO_L05P_0_P93") (pintype "bidirectional"))
    )
    (net (code "84") (name "unconnected-(U$3A-IO_L06P_0{slash}VREF_0-PadP98)") (class "Default")
      (node (ref "U$3") (pin "P98") (pinfunction "IO_L06P_0/VREF_0_P98") (pintype "bidirectional"))
    )
    (net (code "85") (name "unconnected-(U$3A-IP_0-PadP97)") (class "Default")
      (node (ref "U$3") (pin "P97") (pinfunction "IP_0_P97") (pintype "bidirectional"))
    )
    (net (code "86") (name "unconnected-(U$3A-IP_0{slash}VREF_0-PadP82)") (class "Default")
      (node (ref "U$3") (pin "P82") (pinfunction "IP_0/VREF_0_P82") (pintype "bidirectional"))
    )
    (net (code "87") (name "unconnected-(U$3B-IO_L01N_1-PadP57)") (class "Default")
      (node (ref "U$3") (pin "P57") (pinfunction "IO_L01N_1_P57") (pintype "bidirectional"))
    )
    (net (code "88") (name "unconnected-(U$3B-IO_L01P_1-PadP56)") (class "Default")
      (node (ref "U$3") (pin "P56") (pinfunction "IO_L01P_1_P56") (pintype "bidirectional"))
    )
    (net (code "89") (name "unconnected-(U$3B-IO_L02N_1{slash}RHCLK1-PadP60)") (class "Default")
      (node (ref "U$3") (pin "P60") (pinfunction "IO_L02N_1/RHCLK1_P60") (pintype "bidirectional"))
    )
    (net (code "90") (name "unconnected-(U$3B-IO_L02P_1{slash}RHCLK0-PadP59)") (class "Default")
      (node (ref "U$3") (pin "P59") (pinfunction "IO_L02P_1/RHCLK0_P59") (pintype "bidirectional"))
    )
    (net (code "91") (name "unconnected-(U$3B-IO_L03N_1{slash}TRDY1{slash}RHCLK3-PadP62)") (class "Default")
      (node (ref "U$3") (pin "P62") (pinfunction "IO_L03N_1/TRDY1/RHCLK3_P62") (pintype "bidirectional"))
    )
    (net (code "92") (name "unconnected-(U$3B-IO_L03P_1{slash}RHCLK2-PadP61)") (class "Default")
      (node (ref "U$3") (pin "P61") (pinfunction "IO_L03P_1/RHCLK2_P61") (pintype "bidirectional"))
    )
    (net (code "93") (name "unconnected-(U$3B-IO_L04N_1{slash}RHCLK7-PadP65)") (class "Default")
      (node (ref "U$3") (pin "P65") (pinfunction "IO_L04N_1/RHCLK7_P65") (pintype "bidirectional"))
    )
    (net (code "94") (name "unconnected-(U$3B-IO_L04P_1{slash}IRDY1{slash}RHCLK6-PadP64)") (class "Default")
      (node (ref "U$3") (pin "P64") (pinfunction "IO_L04P_1/IRDY1/RHCLK6_P64") (pintype "bidirectional"))
    )
    (net (code "95") (name "unconnected-(U$3B-IO_L05N_1-PadP71)") (class "Default")
      (node (ref "U$3") (pin "P71") (pinfunction "IO_L05N_1_P71") (pintype "bidirectional"))
    )
    (net (code "96") (name "unconnected-(U$3B-IO_L05P_1-PadP70)") (class "Default")
      (node (ref "U$3") (pin "P70") (pinfunction "IO_L05P_1_P70") (pintype "bidirectional"))
    )
    (net (code "97") (name "unconnected-(U$3B-IO_L06N_1-PadP73)") (class "Default")
      (node (ref "U$3") (pin "P73") (pinfunction "IO_L06N_1_P73") (pintype "bidirectional"))
    )
    (net (code "98") (name "unconnected-(U$3B-IO_L06P_1-PadP72)") (class "Default")
      (node (ref "U$3") (pin "P72") (pinfunction "IO_L06P_1_P72") (pintype "bidirectional"))
    )
    (net (code "99") (name "unconnected-(U$3B-IP_1{slash}VREF_1-PadP68)") (class "Default")
      (node (ref "U$3") (pin "P68") (pinfunction "IP_1/VREF_1_P68") (pintype "bidirectional"))
    )
    (net (code "100") (name "unconnected-(U$3C-IO_2{slash}MOSI{slash}CSI_B-PadP46)") (class "Default")
      (node (ref "U$3") (pin "P46") (pinfunction "IO_2/MOSI/CSI_B_P46") (pintype "bidirectional"))
    )
    (net (code "101") (name "unconnected-(U$3C-IO_L02N_2{slash}CSO_B-PadP27)") (class "Default")
      (node (ref "U$3") (pin "P27") (pinfunction "IO_L02N_2/CSO_B_P27") (pintype "bidirectional"))
    )
    (net (code "102") (name "unconnected-(U$3C-IO_L03N_2{slash}VS2-PadP29)") (class "Default")
      (node (ref "U$3") (pin "P29") (pinfunction "IO_L03N_2/VS2_P29") (pintype "bidirectional"))
    )
    (net (code "103") (name "unconnected-(U$3C-IO_L03P_2{slash}RDWR_B-PadP28)") (class "Default")
      (node (ref "U$3") (pin "P28") (pinfunction "IO_L03P_2/RDWR_B_P28") (pintype "bidirectional"))
    )
    (net (code "104") (name "unconnected-(U$3C-IO_L04N_2{slash}VS0-PadP31)") (class "Default")
      (node (ref "U$3") (pin "P31") (pinfunction "IO_L04N_2/VS0_P31") (pintype "bidirectional"))
    )
    (net (code "105") (name "unconnected-(U$3C-IO_L04P_2{slash}VS1-PadP30)") (class "Default")
      (node (ref "U$3") (pin "P30") (pinfunction "IO_L04P_2/VS1_P30") (pintype "bidirectional"))
    )
    (net (code "106") (name "unconnected-(U$3C-IO_L05N_2-PadP33)") (class "Default")
      (node (ref "U$3") (pin "P33") (pinfunction "IO_L05N_2_P33") (pintype "bidirectional"))
    )
    (net (code "107") (name "unconnected-(U$3C-IO_L05P_2-PadP32)") (class "Default")
      (node (ref "U$3") (pin "P32") (pinfunction "IO_L05P_2_P32") (pintype "bidirectional"))
    )
    (net (code "108") (name "unconnected-(U$3C-IO_L06N_2{slash}D6-PadP35)") (class "Default")
      (node (ref "U$3") (pin "P35") (pinfunction "IO_L06N_2/D6_P35") (pintype "bidirectional"))
    )
    (net (code "109") (name "unconnected-(U$3C-IO_L06P_2{slash}D7-PadP34)") (class "Default")
      (node (ref "U$3") (pin "P34") (pinfunction "IO_L06P_2/D7_P34") (pintype "bidirectional"))
    )
    (net (code "110") (name "unconnected-(U$3C-IO_L07P_2{slash}D5-PadP36)") (class "Default")
      (node (ref "U$3") (pin "P36") (pinfunction "IO_L07P_2/D5_P36") (pintype "bidirectional"))
    )
    (net (code "111") (name "unconnected-(U$3C-IO_L07_2{slash}D4-PadP37)") (class "Default")
      (node (ref "U$3") (pin "P37") (pinfunction "IO_L07_2/D4_P37") (pintype "bidirectional"))
    )
    (net (code "112") (name "unconnected-(U$3C-IO_L08N_2{slash}GCLK15-PadP41)") (class "Default")
      (node (ref "U$3") (pin "P41") (pinfunction "IO_L08N_2/GCLK15_P41") (pintype "bidirectional"))
    )
    (net (code "113") (name "unconnected-(U$3C-IO_L08P_2{slash}GCLK14-PadP40)") (class "Default")
      (node (ref "U$3") (pin "P40") (pinfunction "IO_L08P_2/GCLK14_P40") (pintype "bidirectional"))
    )
    (net (code "114") (name "unconnected-(U$3C-IO_L09N_2{slash}GCLK1-PadP44)") (class "Default")
      (node (ref "U$3") (pin "P44") (pinfunction "IO_L09N_2/GCLK1_P44") (pintype "bidirectional"))
    )
    (net (code "115") (name "unconnected-(U$3C-IO_L09P_2{slash}GCLK0-PadP43)") (class "Default")
      (node (ref "U$3") (pin "P43") (pinfunction "IO_L09P_2/GCLK0_P43") (pintype "bidirectional"))
    )
    (net (code "116") (name "unconnected-(U$3C-IO_L10N_2{slash}D3-PadP49)") (class "Default")
      (node (ref "U$3") (pin "P49") (pinfunction "IO_L10N_2/D3_P49") (pintype "bidirectional"))
    )
    (net (code "117") (name "unconnected-(U$3C-IO_L11N_2{slash}D1-PadP52)") (class "Default")
      (node (ref "U$3") (pin "P52") (pinfunction "IO_L11N_2/D1_P52") (pintype "bidirectional"))
    )
    (net (code "118") (name "unconnected-(U$3C-IO_L11P_2{slash}D2-PadP50)") (class "Default")
      (node (ref "U$3") (pin "P50") (pinfunction "IO_L11P_2/D2_P50") (pintype "bidirectional"))
    )
    (net (code "119") (name "unconnected-(U$3C-IP_2{slash}VREF_2-PadP39)") (class "Default")
      (node (ref "U$3") (pin "P39") (pinfunction "IP_2/VREF_2_P39") (pintype "bidirectional"))
    )
    (net (code "120") (name "unconnected-(U$3D-IO_L03N_3{slash}LHCLK1-PadP10)") (class "Default")
      (node (ref "U$3") (pin "P10") (pinfunction "IO_L03N_3/LHCLK1_P10") (pintype "bidirectional"))
    )
    (net (code "121") (name "unconnected-(U$3D-IO_L03P_3{slash}LHCLK0-PadP9)") (class "Default")
      (node (ref "U$3") (pin "P9") (pinfunction "IO_L03P_3/LHCLK0_P9") (pintype "bidirectional"))
    )
    (net (code "122") (name "unconnected-(U$3D-IO_L04P_3{slash}LHCLK2-PadP12)") (class "Default")
      (node (ref "U$3") (pin "P12") (pinfunction "IO_L04P_3/LHCLK2_P12") (pintype "bidirectional"))
    )
    (net (code "123") (name "unconnected-(U$3D-IO_L06N_3-PadP20)") (class "Default")
      (node (ref "U$3") (pin "P20") (pinfunction "IO_L06N_3_P20") (pintype "bidirectional"))
    )
    (net (code "124") (name "unconnected-(U$3D-IO_L06P_3-PadP19)") (class "Default")
      (node (ref "U$3") (pin "P19") (pinfunction "IO_L06P_3_P19") (pintype "bidirectional"))
    )
    (net (code "125") (name "unconnected-(U$3D-IP_3-PadP21)") (class "Default")
      (node (ref "U$3") (pin "P21") (pinfunction "IP_3_P21") (pintype "bidirectional"))
    )
    (net (code "126") (name "unconnected-(U$3D-IP_3{slash}VREF_3-PadP7)") (class "Default")
      (node (ref "U$3") (pin "P7") (pinfunction "IP_3/VREF_3_P7") (pintype "bidirectional"))
    )
    (net (code "127") (name "unconnected-(U8-(DNC)-Pad16)") (class "Default")
      (node (ref "U8") (pin "16") (pinfunction "(DNC)_16") (pintype "no_connect"))
    )
    (net (code "128") (name "unconnected-(U8-(DNC)_2-Pad12)") (class "Default")
      (node (ref "U8") (pin "12") (pinfunction "(DNC)_2_12") (pintype "no_connect"))
    )
    (net (code "129") (name "unconnected-(U8-(DNC)_3-Pad2)") (class "Default")
      (node (ref "U8") (pin "2") (pinfunction "(DNC)_3_2") (pintype "no_connect"))
    )
    (net (code "130") (name "unconnected-(U8-(DNC)_4-Pad15)") (class "Default")
      (node (ref "U8") (pin "15") (pinfunction "(DNC)_4_15") (pintype "no_connect"))
    )
    (net (code "131") (name "unconnected-(U8-(DNC)_5-Pad9)") (class "Default")
      (node (ref "U8") (pin "9") (pinfunction "(DNC)_5_9") (pintype "no_connect"))
    )
    (net (code "132") (name "unconnected-(U8-(DNC)_6-Pad14)") (class "Default")
      (node (ref "U8") (pin "14") (pinfunction "(DNC)_6_14") (pintype "no_connect"))
    )
    (net (code "133") (name "unconnected-(U8-~{CEO}-Pad13)") (class "Default")
      (node (ref "U8") (pin "13") (pinfunction "~{CEO}_13") (pintype "output"))
    )
  )
)
